# Sapflux-Basic_AltA.net
KiCad netlist of a schematic drawn in EAGLE
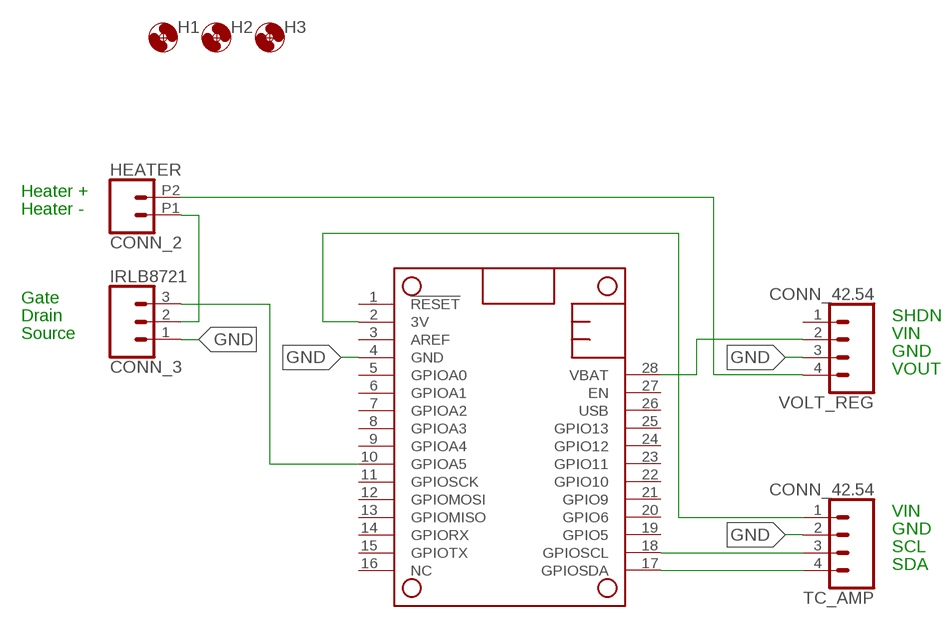
[diagram p0: schematic, sheet 1]

(export (version "E")
  (design (tool "Eeschema 10.0.6"))
  (components
    (comp (ref "H1")
      (value "MOUNTING_HOLE4_NP")
      (footprint "eagle-import:4_40")
      (fields (field (name "MPN") "DNP"))
      (libsource (lib "eagle-import") (part "MOUNTING_HOLE4_NP"))
    )
    (comp (ref "H2")
      (value "MOUNTING_HOLE4_NP")
      (footprint "eagle-import:4_40")
      (fields (field (name "MPN") "DNP"))
      (libsource (lib "eagle-import") (part "MOUNTING_HOLE4_NP"))
    )
    (comp (ref "H3")
      (value "MOUNTING_HOLE4_NP")
      (footprint "eagle-import:4_40")
      (fields (field (name "MPN") "DNP"))
      (libsource (lib "eagle-import") (part "MOUNTING_HOLE4_NP"))
    )
    (comp (ref "HEATER")
      (value "CONN_2")
      (footprint "eagle-import:1X02_2.54_SCREWTERM_ROUND")
      (fields (field (name "MF") "OnShore") (field (name "MPN") "OSTVN02A150"))
      (libsource (lib "eagle-import") (part "CONN_022.54_SCREW_ROUND"))
    )
    (comp (ref "IRLB8721")
      (value "CONN_3")
      (footprint "eagle-import:1X03")
      (libsource (lib "eagle-import") (part "CONN_3"))
    )
    (comp (ref "MS1")
      (value "FEATHERWINGLAYOUT")
      (footprint "eagle-import:FEATHERWING_MIN")
      (libsource (lib "eagle-import") (part "FEATHERWINGLAYOUT"))
    )
    (comp (ref "TC_AMP")
      (value "CONN_42.54")
      (footprint "eagle-import:1X04")
      (libsource (lib "eagle-import") (part "CONN_42.54"))
    )
    (comp (ref "VOLT_REG")
      (value "CONN_42.54")
      (footprint "eagle-import:1X04")
      (libsource (lib "eagle-import") (part "CONN_42.54"))
    )
  )
  (nets
    (net (code "1") (name "/USB") (class "Default")
      (node (ref "MS1") (pin "26") (pinfunction "USB_26") (pintype "power_in"))
    )
    (net (code "2") (name "GND") (class "Default")
      (node (ref "IRLB8721") (pin "1") (pinfunction "1_1") (pintype "passive"))
      (node (ref "MS1") (pin "4") (pinfunction "GND_4") (pintype "power_in"))
      (node (ref "TC_AMP") (pin "2") (pinfunction "2_2") (pintype "passive"))
      (node (ref "VOLT_REG") (pin "3") (pinfunction "3_3") (pintype "passive"))
    )
    (net (code "3") (name "Net-(HEATER-1)") (class "Default")
      (node (ref "HEATER") (pin "P1") (pinfunction "1_P1") (pintype "passive"))
      (node (ref "IRLB8721") (pin "2") (pinfunction "2_2") (pintype "passive"))
    )
    (net (code "4") (name "Net-(HEATER-2)") (class "Default")
      (node (ref "HEATER") (pin "P2") (pinfunction "2_P2") (pintype "passive"))
      (node (ref "VOLT_REG") (pin "4") (pinfunction "4_4") (pintype "passive"))
    )
    (net (code "5") (name "Net-(MS1-3V)") (class "Default")
      (node (ref "MS1") (pin "2") (pinfunction "3V_2") (pintype "power_in"))
      (node (ref "TC_AMP") (pin "1") (pinfunction "1_1") (pintype "passive"))
    )
    (net (code "6") (name "Net-(MS1-GPIOA5)") (class "Default")
      (node (ref "IRLB8721") (pin "3") (pinfunction "3_3") (pintype "passive"))
      (node (ref "MS1") (pin "10") (pinfunction "GPIOA5_10") (pintype "bidirectional"))
    )
    (net (code "7") (name "Net-(MS1-GPIOSCL)") (class "Default")
      (node (ref "MS1") (pin "18") (pinfunction "GPIOSCL_18") (pintype "bidirectional"))
      (node (ref "TC_AMP") (pin "3") (pinfunction "3_3") (pintype "passive"))
    )
    (net (code "8") (name "Net-(MS1-GPIOSDA)") (class "Default")
      (node (ref "MS1") (pin "17") (pinfunction "GPIOSDA_17") (pintype "bidirectional"))
      (node (ref "TC_AMP") (pin "4") (pinfunction "4_4") (pintype "passive"))
    )
    (net (code "9") (name "Net-(MS1-VBAT)") (class "Default")
      (node (ref "MS1") (pin "28") (pinfunction "VBAT_28") (pintype "power_in"))
      (node (ref "VOLT_REG") (pin "2") (pinfunction "2_2") (pintype "passive"))
    )
    (net (code "10") (name "unconnected-(MS1-AREF-Pad3)") (class "Default")
      (node (ref "MS1") (pin "3") (pinfunction "AREF_3") (pintype "passive"))
    )
    (net (code "11") (name "unconnected-(MS1-EN-Pad27)") (class "Default")
      (node (ref "MS1") (pin "27") (pinfunction "EN_27") (pintype "passive"))
    )
    (net (code "12") (name "unconnected-(MS1-GPIO5-Pad19)") (class "Default")
      (node (ref "MS1") (pin "19") (pinfunction "GPIO5_19") (pintype "bidirectional"))
    )
    (net (code "13") (name "unconnected-(MS1-GPIO6-Pad20)") (class "Default")
      (node (ref "MS1") (pin "20") (pinfunction "GPIO6_20") (pintype "bidirectional"))
    )
    (net (code "14") (name "unconnected-(MS1-GPIO9-Pad21)") (class "Default")
      (node (ref "MS1") (pin "21") (pinfunction "GPIO9_21") (pintype "bidirectional"))
    )
    (net (code "15") (name "unconnected-(MS1-GPIO10-Pad22)") (class "Default")
      (node (ref "MS1") (pin "22") (pinfunction "GPIO10_22") (pintype "bidirectional"))
    )
    (net (code "16") (name "unconnected-(MS1-GPIO11-Pad23)") (class "Default")
      (node (ref "MS1") (pin "23") (pinfunction "GPIO11_23") (pintype "bidirectional"))
    )
    (net (code "17") (name "unconnected-(MS1-GPIO12-Pad24)") (class "Default")
      (node (ref "MS1") (pin "24") (pinfunction "GPIO12_24") (pintype "bidirectional"))
    )
    (net (code "18") (name "unconnected-(MS1-GPIO13-Pad25)") (class "Default")
      (node (ref "MS1") (pin "25") (pinfunction "GPIO13_25") (pintype "bidirectional"))
    )
    (net (code "19") (name "unconnected-(MS1-GPIOA0-Pad5)") (class "Default")
      (node (ref "MS1") (pin "5") (pinfunction "GPIOA0_5") (pintype "bidirectional"))
    )
    (net (code "20") (name "unconnected-(MS1-GPIOA1-Pad6)") (class "Default")
      (node (ref "MS1") (pin "6") (pinfunction "GPIOA1_6") (pintype "bidirectional"))
    )
    (net (code "21") (name "unconnected-(MS1-GPIOA2-Pad7)") (class "Default")
      (node (ref "MS1") (pin "7") (pinfunction "GPIOA2_7") (pintype "bidirectional"))
    )
    (net (code "22") (name "unconnected-(MS1-GPIOA3-Pad8)") (class "Default")
      (node (ref "MS1") (pin "8") (pinfunction "GPIOA3_8") (pintype "bidirectional"))
    )
    (net (code "23") (name "unconnected-(MS1-GPIOA4-Pad9)") (class "Default")
      (node (ref "MS1") (pin "9") (pinfunction "GPIOA4_9") (pintype "bidirectional"))
    )
    (net (code "24") (name "unconnected-(MS1-GPIOMISO-Pad13)") (class "Default")
      (node (ref "MS1") (pin "13") (pinfunction "GPIOMISO_13") (pintype "bidirectional"))
    )
    (net (code "25") (name "unconnected-(MS1-GPIOMOSI-Pad12)") (class "Default")
      (node (ref "MS1") (pin "12") (pinfunction "GPIOMOSI_12") (pintype "bidirectional"))
    )
    (net (code "26") (name "unconnected-(MS1-GPIORX-Pad14)") (class "Default")
      (node (ref "MS1") (pin "14") (pinfunction "GPIORX_14") (pintype "bidirectional"))
    )
    (net (code "27") (name "unconnected-(MS1-GPIOSCK-Pad11)") (class "Default")
      (node (ref "MS1") (pin "11") (pinfunction "GPIOSCK_11") (pintype "bidirectional"))
    )
    (net (code "28") (name "unconnected-(MS1-GPIOTX-Pad15)") (class "Default")
      (node (ref "MS1") (pin "15") (pinfunction "GPIOTX_15") (pintype "bidirectional"))
    )
    (net (code "29") (name "unconnected-(MS1-NC-Pad16)") (class "Default")
      (node (ref "MS1") (pin "16") (pinfunction "NC_16") (pintype "passive"))
    )
    (net (code "30") (name "unconnected-(MS1-~{RESET}-Pad1)") (class "Default")
      (node (ref "MS1") (pin "1") (pinfunction "~{RESET}_1") (pintype "input"))
    )
    (net (code "31") (name "unconnected-(VOLT_REG-Pad1)") (class "Default")
      (node (ref "VOLT_REG") (pin "1") (pinfunction "1_1") (pintype "passive"))
    )
  )
)
